# design.net
KiCad netlist of a schematic drawn in EasyEDA Pro
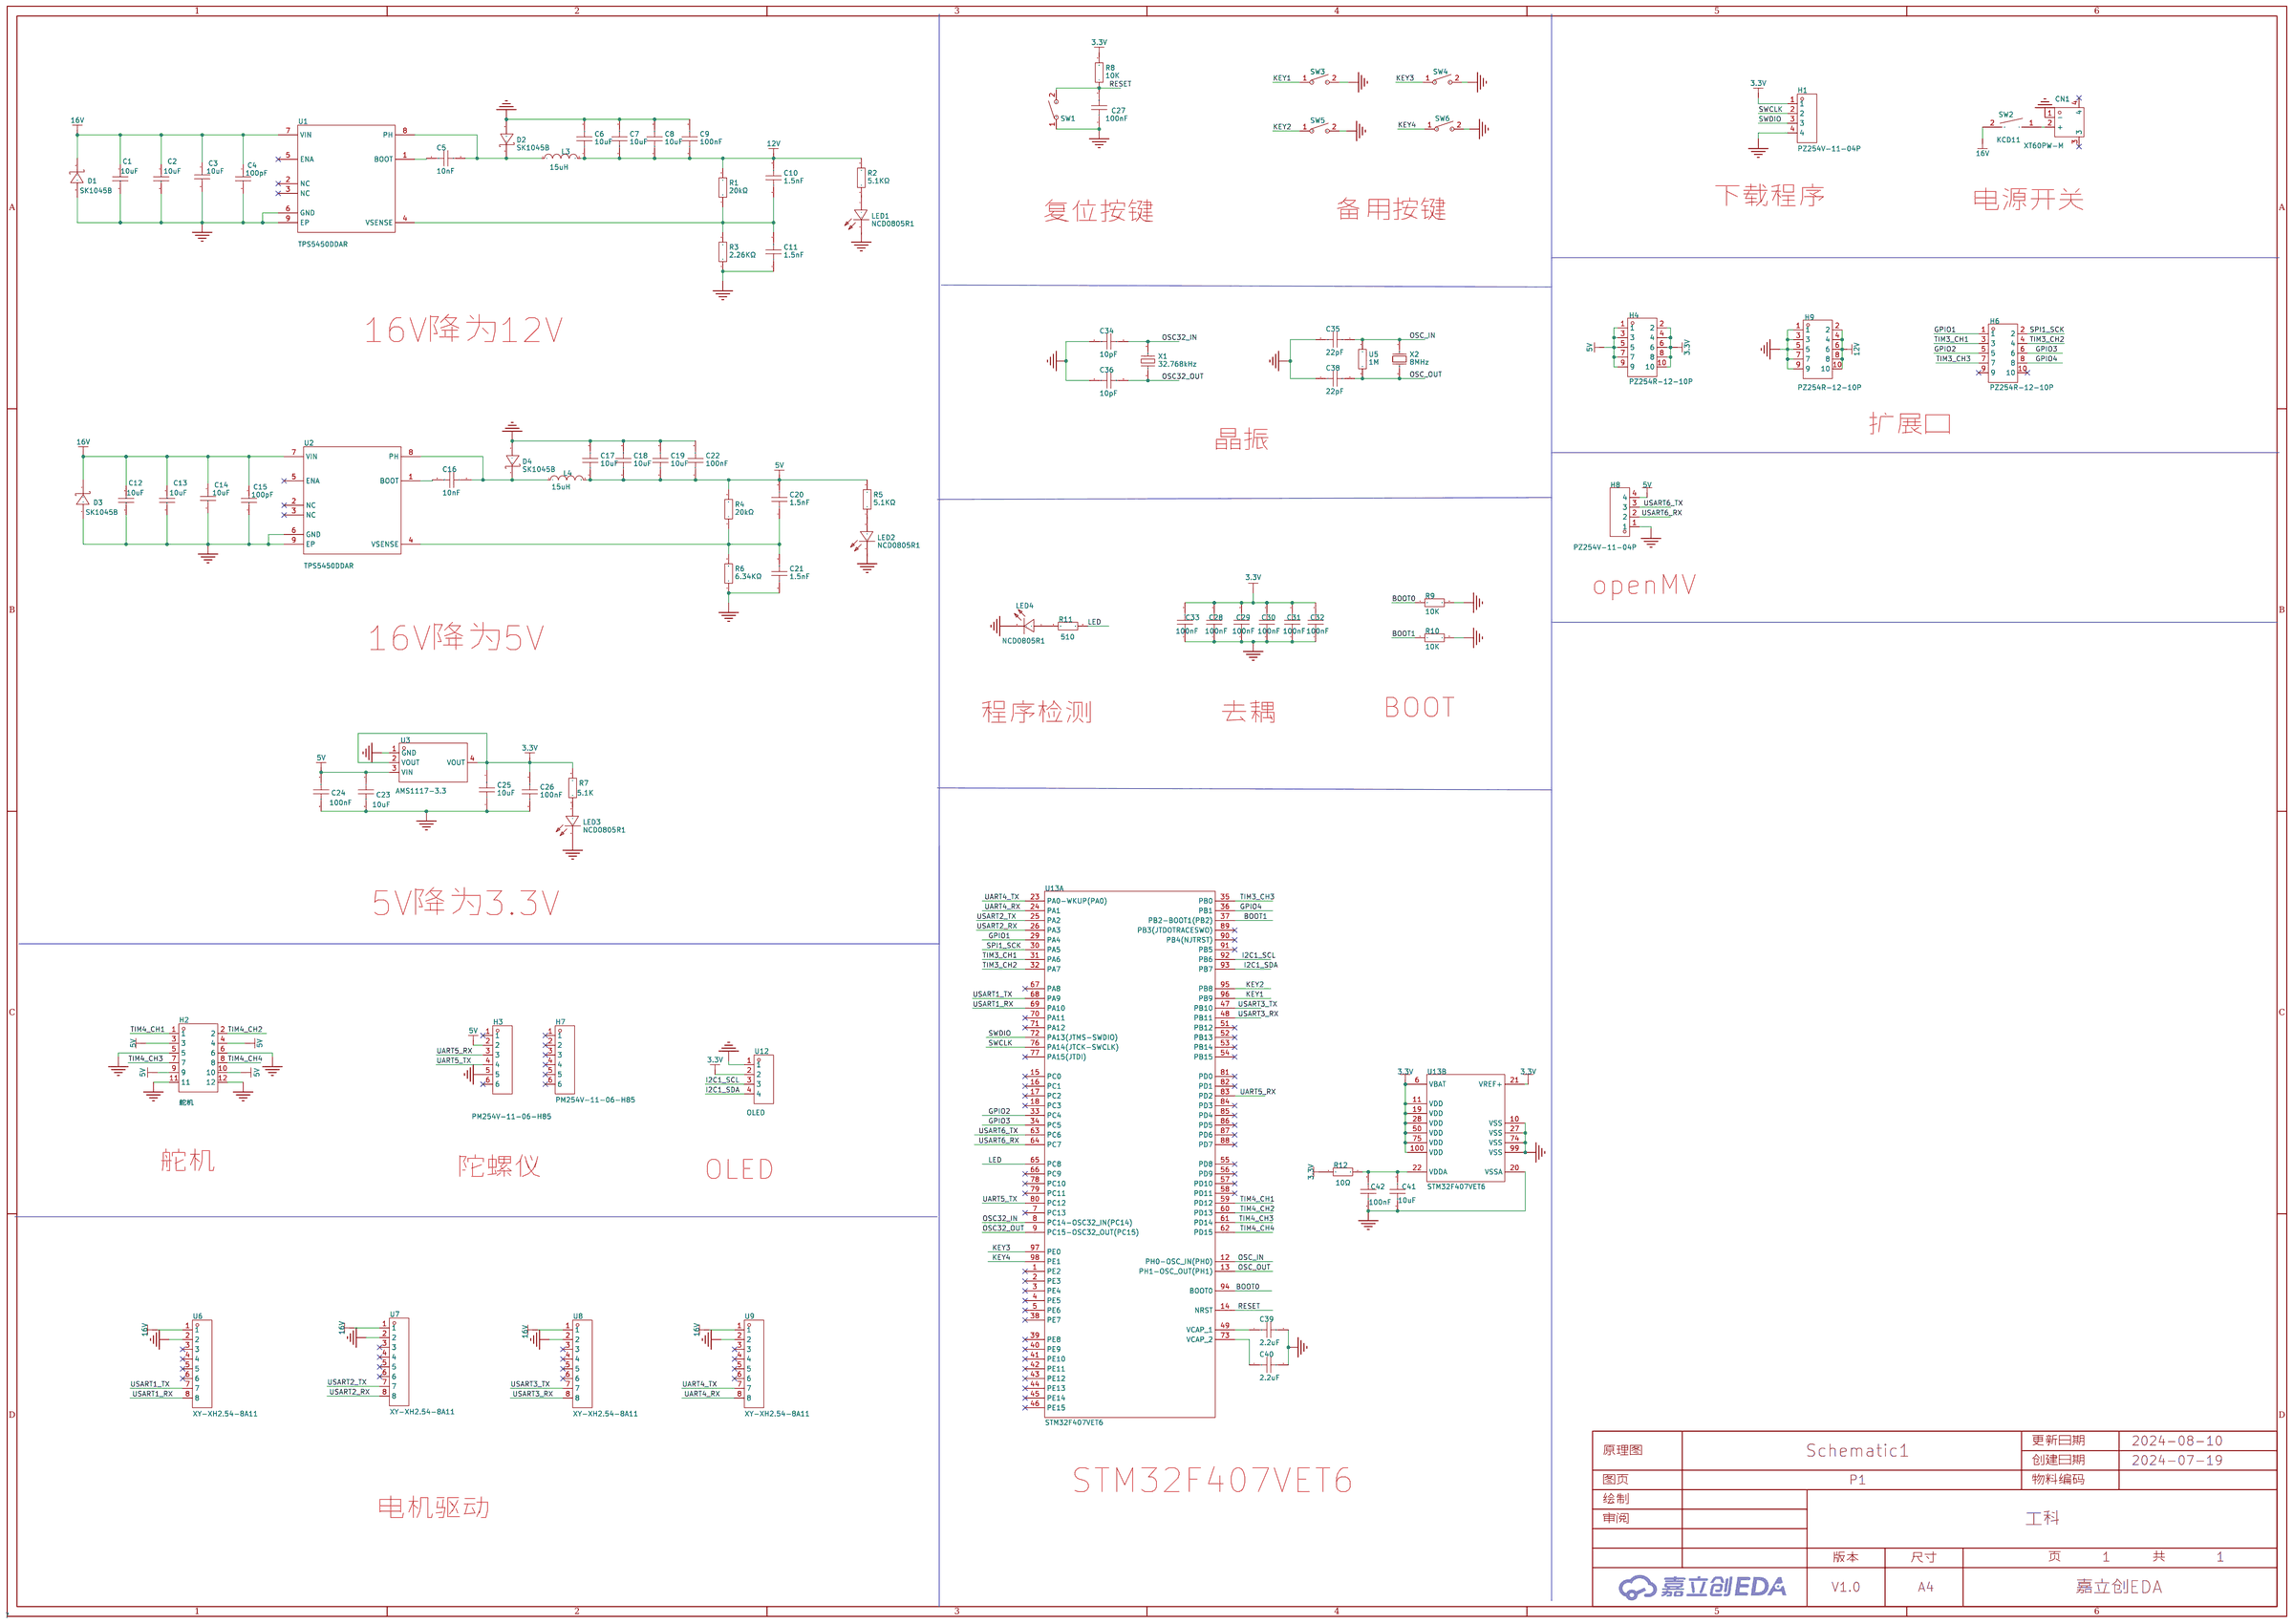
[diagram p0: schematic sheet]

(export (version "E")
  (design (tool "Eeschema 10.0.6"))
  (components
    (comp (ref "C1")
      (value "10uF")
      (footprint "easyedapro:C0805")
      (description "容值:100nF;精度:±10%;额定电压:50V;材质(温度系数):X7R;")
      (fields
        (field (name "Manufacturer Part") "CC0805KRX7R9BB104")
        (field (name "Manufacturer") "YAGEO(国巨)")
      )
      (libsource (lib "easyedapro") (part "CC0805KRX7R9BB104"))
    )
    (comp (ref "C2")
      (value "10uF")
      (footprint "easyedapro:C0805")
      (description "容值:100nF;精度:±10%;额定电压:50V;材质(温度系数):X7R;")
      (fields
        (field (name "Manufacturer Part") "CC0805KRX7R9BB104")
        (field (name "Manufacturer") "YAGEO(国巨)")
      )
      (libsource (lib "easyedapro") (part "CC0805KRX7R9BB104"))
    )
    (comp (ref "C3")
      (value "10uF")
      (footprint "easyedapro:C0805")
      (description "容值:100nF;精度:±10%;额定电压:50V;材质(温度系数):X7R;")
      (fields
        (field (name "Manufacturer Part") "CC0805KRX7R9BB104")
        (field (name "Manufacturer") "YAGEO(国巨)")
      )
      (libsource (lib "easyedapro") (part "CC0805KRX7R9BB104"))
    )
    (comp (ref "C4")
      (value "100pF")
      (footprint "easyedapro:C0805")
      (description "容值:100nF;精度:±10%;额定电压:50V;材质(温度系数):X7R;")
      (fields
        (field (name "Manufacturer Part") "CC0805KRX7R9BB104")
        (field (name "Manufacturer") "YAGEO(国巨)")
      )
      (libsource (lib "easyedapro") (part "CC0805KRX7R9BB104"))
    )
    (comp (ref "C5")
      (value "10nF")
      (footprint "easyedapro:C0805")
      (libsource (lib "easyedapro") (part "CapAcitance"))
    )
    (comp (ref "C6")
      (value "10uF")
      (footprint "easyedapro:C0805")
      (libsource (lib "easyedapro") (part "CapAcitance"))
    )
    (comp (ref "C7")
      (value "10uF")
      (footprint "easyedapro:C0805")
      (libsource (lib "easyedapro") (part "CapAcitance"))
    )
    (comp (ref "C8")
      (value "10uF")
      (footprint "easyedapro:C0805")
      (libsource (lib "easyedapro") (part "CapAcitance"))
    )
    (comp (ref "C9")
      (value "100nF")
      (footprint "easyedapro:C0805")
      (libsource (lib "easyedapro") (part "CapAcitance"))
    )
    (comp (ref "C10")
      (value "1.5nF")
      (footprint "easyedapro:C0805")
      (libsource (lib "easyedapro") (part "CapAcitance"))
    )
    (comp (ref "C11")
      (value "1.5nF")
      (footprint "easyedapro:C0805")
      (libsource (lib "easyedapro") (part "CapAcitance"))
    )
    (comp (ref "C12")
      (value "10uF")
      (footprint "easyedapro:C0805")
      (description "容值:100nF;精度:±10%;额定电压:50V;材质(温度系数):X7R;")
      (fields
        (field (name "Manufacturer Part") "CC0805KRX7R9BB104")
        (field (name "Manufacturer") "YAGEO(国巨)")
      )
      (libsource (lib "easyedapro") (part "CC0805KRX7R9BB104"))
    )
    (comp (ref "C13")
      (value "10uF")
      (footprint "easyedapro:C0805")
      (description "容值:100nF;精度:±10%;额定电压:50V;材质(温度系数):X7R;")
      (fields
        (field (name "Manufacturer Part") "CC0805KRX7R9BB104")
        (field (name "Manufacturer") "YAGEO(国巨)")
      )
      (libsource (lib "easyedapro") (part "CC0805KRX7R9BB104"))
    )
    (comp (ref "C14")
      (value "10uF")
      (footprint "easyedapro:C0805")
      (description "容值:100nF;精度:±10%;额定电压:50V;材质(温度系数):X7R;")
      (fields
        (field (name "Manufacturer Part") "CC0805KRX7R9BB104")
        (field (name "Manufacturer") "YAGEO(国巨)")
      )
      (libsource (lib "easyedapro") (part "CC0805KRX7R9BB104"))
    )
    (comp (ref "C15")
      (value "100pF")
      (footprint "easyedapro:C0805")
      (description "容值:100nF;精度:±10%;额定电压:50V;材质(温度系数):X7R;")
      (fields
        (field (name "Manufacturer Part") "CC0805KRX7R9BB104")
        (field (name "Manufacturer") "YAGEO(国巨)")
      )
      (libsource (lib "easyedapro") (part "CC0805KRX7R9BB104"))
    )
    (comp (ref "C16")
      (value "10nF")
      (footprint "easyedapro:C0805")
      (libsource (lib "easyedapro") (part "CapAcitance"))
    )
    (comp (ref "C17")
      (value "10uF")
      (footprint "easyedapro:C0805")
      (libsource (lib "easyedapro") (part "CapAcitance"))
    )
    (comp (ref "C18")
      (value "10uF")
      (footprint "easyedapro:C0805")
      (libsource (lib "easyedapro") (part "CapAcitance"))
    )
    (comp (ref "C19")
      (value "10uF")
      (footprint "easyedapro:C0805")
      (libsource (lib "easyedapro") (part "CapAcitance"))
    )
    (comp (ref "C20")
      (value "1.5nF")
      (footprint "easyedapro:C0805")
      (libsource (lib "easyedapro") (part "CapAcitance"))
    )
    (comp (ref "C21")
      (value "1.5nF")
      (footprint "easyedapro:C0805")
      (libsource (lib "easyedapro") (part "CapAcitance"))
    )
    (comp (ref "C22")
      (value "100nF")
      (footprint "easyedapro:C0805")
      (libsource (lib "easyedapro") (part "CapAcitance"))
    )
    (comp (ref "C23")
      (value "10uF")
      (footprint "easyedapro:C0805")
      (libsource (lib "easyedapro") (part "CapAcitance"))
    )
    (comp (ref "C24")
      (value "100nF")
      (footprint "easyedapro:C0805")
      (libsource (lib "easyedapro") (part "CapAcitance"))
    )
    (comp (ref "C25")
      (value "10uF")
      (footprint "easyedapro:C0805")
      (libsource (lib "easyedapro") (part "CapAcitance"))
    )
    (comp (ref "C26")
      (value "100nF")
      (footprint "easyedapro:C0805")
      (libsource (lib "easyedapro") (part "CapAcitance"))
    )
    (comp (ref "C27")
      (value "100nF")
      (footprint "easyedapro:C0805")
      (libsource (lib "easyedapro") (part "CapAcitance"))
    )
    (comp (ref "C28")
      (value "100nF")
      (footprint "easyedapro:C0805")
      (libsource (lib "easyedapro") (part "CapAcitance"))
    )
    (comp (ref "C29")
      (value "100nF")
      (footprint "easyedapro:C0805")
      (libsource (lib "easyedapro") (part "CapAcitance"))
    )
    (comp (ref "C30")
      (value "100nF")
      (footprint "easyedapro:C0805")
      (libsource (lib "easyedapro") (part "CapAcitance"))
    )
    (comp (ref "C31")
      (value "100nF")
      (footprint "easyedapro:C0805")
      (libsource (lib "easyedapro") (part "CapAcitance"))
    )
    (comp (ref "C32")
      (value "100nF")
      (footprint "easyedapro:C0805")
      (libsource (lib "easyedapro") (part "CapAcitance"))
    )
    (comp (ref "C33")
      (value "100nF")
      (footprint "easyedapro:C0805")
      (libsource (lib "easyedapro") (part "CapAcitance"))
    )
    (comp (ref "C34")
      (value "10pF")
      (footprint "easyedapro:C0805")
      (libsource (lib "easyedapro") (part "CapAcitance"))
    )
    (comp (ref "C35")
      (value "22pF")
      (footprint "easyedapro:C0805")
      (libsource (lib "easyedapro") (part "CapAcitance"))
    )
    (comp (ref "C36")
      (value "10pF")
      (footprint "easyedapro:C0805")
      (libsource (lib "easyedapro") (part "CapAcitance"))
    )
    (comp (ref "C38")
      (value "22pF")
      (footprint "easyedapro:C0805")
      (libsource (lib "easyedapro") (part "CapAcitance"))
    )
    (comp (ref "C39")
      (value "2.2uF")
      (footprint "easyedapro:C0805")
      (libsource (lib "easyedapro") (part "CapAcitance"))
    )
    (comp (ref "C40")
      (value "2.2uF")
      (footprint "easyedapro:C0805")
      (libsource (lib "easyedapro") (part "CapAcitance"))
    )
    (comp (ref "C41")
      (value "10uF")
      (footprint "easyedapro:C0805")
      (libsource (lib "easyedapro") (part "CapAcitance"))
    )
    (comp (ref "C42")
      (value "100nF")
      (footprint "easyedapro:C0805")
      (libsource (lib "easyedapro") (part "CapAcitance"))
    )
    (comp (ref "CN1")
      (value "XT60PW-M")
      (footprint "easyedapro:CONN-TH_XT60PW-M")
      (description "类别:-;类型1:-;")
      (fields (field (name "Manufacturer") "AMASS(艾迈斯)"))
      (libsource (lib "easyedapro") (part "XT60PW-M"))
    )
    (comp (ref "D1")
      (value "SK1045B")
      (footprint "easyedapro:SMB_L4.6-W3.6-LS5.3-RD")
      (description "二极管配置:独立式;正向压降(Vf):550mV@10A;直流反向耐压(Vr):45V;整流电流:10A;")
      (fields (field (name "Manufacturer") "MDD(辰达半导体)"))
      (libsource (lib "easyedapro") (part "SK1045_C65017"))
    )
    (comp (ref "D2")
      (value "SK1045B")
      (footprint "easyedapro:SMB_L4.6-W3.6-LS5.3-RD")
      (description "二极管配置:独立式;正向压降(Vf):550mV@10A;直流反向耐压(Vr):45V;整流电流:10A;")
      (fields (field (name "Manufacturer") "MDD(辰达半导体)"))
      (libsource (lib "easyedapro") (part "SK1045_C65017"))
    )
    (comp (ref "D3")
      (value "SK1045B")
      (footprint "easyedapro:SMB_L4.6-W3.6-LS5.3-RD")
      (description "二极管配置:独立式;正向压降(Vf):550mV@10A;直流反向耐压(Vr):45V;整流电流:10A;")
      (fields (field (name "Manufacturer") "MDD(辰达半导体)"))
      (libsource (lib "easyedapro") (part "SK1045_C65017"))
    )
    (comp (ref "D4")
      (value "SK1045B")
      (footprint "easyedapro:SMB_L4.6-W3.6-LS5.3-RD")
      (description "二极管配置:独立式;正向压降(Vf):550mV@10A;直流反向耐压(Vr):45V;整流电流:10A;")
      (fields (field (name "Manufacturer") "MDD(辰达半导体)"))
      (libsource (lib "easyedapro") (part "SK1045_C65017"))
    )
    (comp (ref "H1")
      (value "PZ254V-11-04P")
      (footprint "easyedapro:HDR-TH_4P-P2.54-V-M")
      (fields (field (name "Manufacturer") "XFCN(兴飞)"))
      (libsource (lib "easyedapro") (part "PZ254V-11-04P_C2691448"))
    )
    (comp (ref "H2")
      (value "舵机")
      (footprint "easyedapro:HDR-TH_12P-P2.54-H-M-R2-C6-S2.54")
      (fields (field (name "Manufacturer") "XFCN(兴飞)"))
      (libsource (lib "easyedapro") (part "PZ254R-12-12P"))
    )
    (comp (ref "H3")
      (value "PM254V-11-06-H85")
      (footprint "easyedapro:HDR-TH_6P-P2.54-V-F")
      (fields (field (name "Manufacturer") "XFCN(兴飞)"))
      (libsource (lib "easyedapro") (part "PM254V-11-06-H85"))
    )
    (comp (ref "H4")
      (value "PZ254R-12-10P")
      (footprint "easyedapro:HDR-TH_10P-P2.54-H-M-R2-C5-S2.54")
      (fields (field (name "Manufacturer") "XFCN(兴飞)"))
      (libsource (lib "easyedapro") (part "PZ254R-12-10P"))
    )
    (comp (ref "H6")
      (value "PZ254R-12-10P")
      (footprint "easyedapro:HDR-TH_10P-P2.54-H-M-R2-C5-S2.54")
      (fields (field (name "Manufacturer") "XFCN(兴飞)"))
      (libsource (lib "easyedapro") (part "PZ254R-12-10P"))
    )
    (comp (ref "H7")
      (value "PM254V-11-06-H85")
      (footprint "easyedapro:HDR-TH_6P-P2.54-V-F")
      (fields (field (name "Manufacturer") "XFCN(兴飞)"))
      (libsource (lib "easyedapro") (part "PM254V-11-06-H85"))
    )
    (comp (ref "H8")
      (value "PZ254V-11-04P")
      (footprint "easyedapro:HDR-TH_4P-P2.54-V-M")
      (fields (field (name "Manufacturer") "XFCN(兴飞)"))
      (libsource (lib "easyedapro") (part "PZ254V-11-04P_C2691448"))
    )
    (comp (ref "H9")
      (value "PZ254R-12-10P")
      (footprint "easyedapro:HDR-TH_10P-P2.54-H-M-R2-C5-S2.54")
      (fields (field (name "Manufacturer") "XFCN(兴飞)"))
      (libsource (lib "easyedapro") (part "PZ254R-12-10P"))
    )
    (comp (ref "L3")
      (value "15uH")
      (footprint "easyedapro:IND-SMD_L11.5-W10.0_APS10A40")
      (description "电感值:15uH;精度:±20%;额定电流:6.55A;饱和电流(Isat):7A;")
      (fields (field (name "Manufacturer Part") "APS10A40M150") (field (name "Manufacturer") "Coilank(驰兴电感)"))
      (libsource (lib "easyedapro") (part "APS10A40M150"))
    )
    (comp (ref "L4")
      (value "15uH")
      (footprint "easyedapro:IND-SMD_L11.5-W10.0_APS10A40")
      (description "电感值:15uH;精度:±20%;额定电流:6.55A;饱和电流(Isat):7A;")
      (fields (field (name "Manufacturer Part") "APS10A40M150") (field (name "Manufacturer") "Coilank(驰兴电感)"))
      (libsource (lib "easyedapro") (part "APS10A40M150"))
    )
    (comp (ref "LED1")
      (value "NCD0805R1")
      (footprint "easyedapro:LED0805-R-RD")
      (fields (field (name "Manufacturer") "国星光电"))
      (libsource (lib "easyedapro") (part "FC-2012HRK-620D"))
    )
    (comp (ref "LED2")
      (value "NCD0805R1")
      (footprint "easyedapro:LED0805-R-RD")
      (fields (field (name "Manufacturer") "国星光电"))
      (libsource (lib "easyedapro") (part "FC-2012HRK-620D"))
    )
    (comp (ref "LED3")
      (value "NCD0805R1")
      (footprint "easyedapro:LED0805-R-RD")
      (fields (field (name "Manufacturer") "国星光电"))
      (libsource (lib "easyedapro") (part "FC-2012HRK-620D"))
    )
    (comp (ref "LED4")
      (value "NCD0805R1")
      (footprint "easyedapro:LED0805-R-RD")
      (fields (field (name "Manufacturer") "国星光电"))
      (libsource (lib "easyedapro") (part "FC-2012HRK-620D"))
    )
    (comp (ref "R1") (value "20kΩ") (footprint "easyedapro:R0805") (libsource (lib "easyedapro") (part "电阻")))
    (comp (ref "R2")
      (value "5.1KΩ")
      (footprint "easyedapro:R0805")
      (libsource (lib "easyedapro") (part "电阻"))
    )
    (comp (ref "R3")
      (value "2.26KΩ")
      (footprint "easyedapro:R0805")
      (libsource (lib "easyedapro") (part "电阻"))
    )
    (comp (ref "R4") (value "20kΩ") (footprint "easyedapro:R0805") (libsource (lib "easyedapro") (part "电阻")))
    (comp (ref "R5")
      (value "5.1KΩ")
      (footprint "easyedapro:R0805")
      (libsource (lib "easyedapro") (part "电阻"))
    )
    (comp (ref "R6")
      (value "6.34KΩ")
      (footprint "easyedapro:R0805")
      (libsource (lib "easyedapro") (part "电阻"))
    )
    (comp (ref "R7") (value "5.1K") (footprint "easyedapro:R0805") (libsource (lib "easyedapro") (part "电阻")))
    (comp (ref "R8") (value "10K") (footprint "easyedapro:R0805") (libsource (lib "easyedapro") (part "电阻")))
    (comp (ref "R9") (value "10K") (footprint "easyedapro:R0805") (libsource (lib "easyedapro") (part "电阻")))
    (comp (ref "R10") (value "10K") (footprint "easyedapro:R0805") (libsource (lib "easyedapro") (part "电阻")))
    (comp (ref "R11") (value "510") (footprint "easyedapro:R0805") (libsource (lib "easyedapro") (part "电阻")))
    (comp (ref "R12") (value "10Ω") (footprint "easyedapro:R0805") (libsource (lib "easyedapro") (part "电阻")))
    (comp (ref "SW1")
      (value "轻触按键3*6*2.5")
      (footprint "easyedapro:SW-SMD_L6.0-W3.6-LS8.0")
      (libsource (lib "easyedapro") (part "轻触按键3*6*2.5"))
    )
    (comp (ref "SW2")
      (value "KCD11")
      (footprint "easyedapro:SW-TH_RS601HL-1010011BB")
      (description "带灯:无;引脚样式:焊片;额定电流:3A;额定电压(AC):250V;额定电压(DC):-;电路结构:单刀单掷;机械寿命:1万次;")
      (fields (field (name "Manufacturer") "HCTL(华灿天禄)"))
      (libsource (lib "easyedapro") (part "RS601HL-1010011BB"))
    )
    (comp (ref "SW3")
      (value "轻触按键3*6*2.5")
      (footprint "easyedapro:SW-SMD_L6.0-W3.6-LS8.0")
      (libsource (lib "easyedapro") (part "轻触按键3*6*2.5"))
    )
    (comp (ref "SW4")
      (value "轻触按键3*6*2.5")
      (footprint "easyedapro:SW-SMD_L6.0-W3.6-LS8.0")
      (libsource (lib "easyedapro") (part "轻触按键3*6*2.5"))
    )
    (comp (ref "SW5")
      (value "轻触按键3*6*2.5")
      (footprint "easyedapro:SW-SMD_L6.0-W3.6-LS8.0")
      (libsource (lib "easyedapro") (part "轻触按键3*6*2.5"))
    )
    (comp (ref "SW6")
      (value "轻触按键3*6*2.5")
      (footprint "easyedapro:SW-SMD_L6.0-W3.6-LS8.0")
      (libsource (lib "easyedapro") (part "轻触按键3*6*2.5"))
    )
    (comp (ref "U1")
      (value "TPS5450DDAR")
      (footprint "easyedapro:SOP-8_L4.9-W3.9-P1.27-LS6.0-BL-EP")
      (description "功能类型:降压型;输出类型:可调;输入电压:5.5V~36V;输出电压:1.221V~31.32V;输出电流(最大值):5A;")
      (fields (field (name "Manufacturer") "TI(德州仪器)"))
      (libsource (lib "easyedapro") (part "TPS5450DDAR"))
    )
    (comp (ref "U2")
      (value "TPS5450DDAR")
      (footprint "easyedapro:SOP-8_L4.9-W3.9-P1.27-LS6.0-BL-EP")
      (description "功能类型:降压型;输出类型:可调;输入电压:5.5V~36V;输出电压:1.221V~31.32V;输出电流(最大值):5A;")
      (fields (field (name "Manufacturer") "TI(德州仪器)"))
      (libsource (lib "easyedapro") (part "TPS5450DDAR"))
    )
    (comp (ref "U3")
      (value "AMS1117-3.3")
      (footprint "easyedapro:SOT-223-3_L6.5-W3.4-P2.30-LS7.0-BR")
      (description "输出类型:固定;最大输入电压:-;输出电压:3.3V;最大输出电流:1A;电源纹波抑制比(PSRR):72dB@(120Hz);输出极性:正极;")
      (fields (field (name "Manufacturer") "AMS"))
      (libsource (lib "easyedapro") (part "AMS1117-3.3"))
    )
    (comp (ref "U5") (value "1M") (footprint "easyedapro:R0805") (libsource (lib "easyedapro") (part "电阻")))
    (comp (ref "U6")
      (value "XY-XH2.54-8A11")
      (footprint "easyedapro:HDR-TH_8P-P2.50-V-F-2")
      (description "插针结构:1x8P;间距:2.54mm;安装方式:直插;总PIN数:8P;排数:1;每排PIN数:8;行距:2.54mm;额定电流:2A;工作温度范围:-25°C~+85°C;")
      (fields (field (name "Manufacturer") "XYECONN(辛译)"))
      (libsource (lib "easyedapro") (part "XY-XH2.54-8A11"))
    )
    (comp (ref "U7")
      (value "XY-XH2.54-8A11")
      (footprint "easyedapro:HDR-TH_8P-P2.50-V-F-2")
      (description "插针结构:1x8P;间距:2.54mm;安装方式:直插;总PIN数:8P;排数:1;每排PIN数:8;行距:2.54mm;额定电流:2A;工作温度范围:-25°C~+85°C;")
      (fields (field (name "Manufacturer") "XYECONN(辛译)"))
      (libsource (lib "easyedapro") (part "XY-XH2.54-8A11"))
    )
    (comp (ref "U8")
      (value "XY-XH2.54-8A11")
      (footprint "easyedapro:HDR-TH_8P-P2.50-V-F-2")
      (description "插针结构:1x8P;间距:2.54mm;安装方式:直插;总PIN数:8P;排数:1;每排PIN数:8;行距:2.54mm;额定电流:2A;工作温度范围:-25°C~+85°C;")
      (fields (field (name "Manufacturer") "XYECONN(辛译)"))
      (libsource (lib "easyedapro") (part "XY-XH2.54-8A11"))
    )
    (comp (ref "U9")
      (value "XY-XH2.54-8A11")
      (footprint "easyedapro:HDR-TH_8P-P2.50-V-F-2")
      (description "插针结构:1x8P;间距:2.54mm;安装方式:直插;总PIN数:8P;排数:1;每排PIN数:8;行距:2.54mm;额定电流:2A;工作温度范围:-25°C~+85°C;")
      (fields (field (name "Manufacturer") "XYECONN(辛译)"))
      (libsource (lib "easyedapro") (part "XY-XH2.54-8A11"))
    )
    (comp (ref "U12")
      (value "OLED")
      (footprint "easyedapro:HDR-TH_4P-P2.54-H-F-W10.0-N")
      (fields (field (name "Manufacturer") "HCTL(华灿天禄)"))
      (libsource (lib "easyedapro") (part "PM254-1-04-W-8.5"))
    )
    (comp (ref "U13")
      (value "STM32F407VET6")
      (footprint "easyedapro:LQFP-100_L14.0-W14.0-P0.50-LS16.0-BL")
      (description "CPU内核:CM4;程序存储容量:512KB;RAM总容量:192KB;GPIO端口数量:82;工作电压范围:1.8V~3.6V;CPU最大主频:168MHz;程序存储器类型:FLASH;")
      (fields (field (name "Manufacturer") "ST(意法半导体)"))
      (libsource (lib "easyedapro") (part "STM32F407VET6"))
    )
    (comp (ref "X1")
      (value "32.768kHz")
      (footprint "easyedapro:OSC-SMD_L3.2-W1.5")
      (description "晶振类型:贴片晶振;频率:32.768kHz;常温频差:±20ppm;外接负载电容:12.5pF;频率稳定度(全温):-;")
      (fields (field (name "Manufacturer Part") "X321532768KGD2SI") (field (name "Manufacturer") "YXC(扬兴晶振)"))
      (libsource (lib "easyedapro") (part "X321532768KGD2SI"))
    )
    (comp (ref "X2")
      (value "8MHz")
      (footprint "easyedapro:HC-49US_L11.5-W4.5-P4.88")
      (description "晶振类型:直插晶振;频率:8MHz;常温频差:±30ppm;外接负载电容:20pF;频率稳定度(全温):±30ppm;")
      (fields (field (name "Manufacturer Part") "TAXD8M2GLFBET2T") (field (name "Manufacturer") "YJX(雅晶鑫)"))
      (libsource (lib "easyedapro") (part "HC-49S 8MHz 20pF 30PPM"))
    )
  )
  (nets
    (net (code "1") (name "/BOOT0") (class "Default")
      (node (ref "R9") (pin "1") (pinfunction "1_1") (pintype "input"))
      (node (ref "U13") (pin "94") (pinfunction "BOOT0_94") (pintype "unspecified"))
    )
    (net (code "2") (name "/BOOT1") (class "Default")
      (node (ref "R10") (pin "1") (pinfunction "1_1") (pintype "input"))
      (node (ref "U13") (pin "37") (pinfunction "PB2-BOOT1(PB2)_37") (pintype "bidirectional"))
    )
    (net (code "3") (name "/GPIO1") (class "Default")
      (node (ref "H6") (pin "1") (pinfunction "1_1") (pintype "unspecified"))
      (node (ref "U13") (pin "29") (pinfunction "PA4_29") (pintype "bidirectional"))
    )
    (net (code "4") (name "/GPIO2") (class "Default")
      (node (ref "H6") (pin "5") (pinfunction "5_5") (pintype "unspecified"))
      (node (ref "U13") (pin "33") (pinfunction "PC4_33") (pintype "bidirectional"))
    )
    (net (code "5") (name "/GPIO3") (class "Default")
      (node (ref "H6") (pin "6") (pinfunction "6_6") (pintype "unspecified"))
      (node (ref "U13") (pin "34") (pinfunction "PC5_34") (pintype "bidirectional"))
    )
    (net (code "6") (name "/GPIO4") (class "Default")
      (node (ref "H6") (pin "8") (pinfunction "8_8") (pintype "unspecified"))
      (node (ref "U13") (pin "36") (pinfunction "PB1_36") (pintype "bidirectional"))
    )
    (net (code "7") (name "/I2C1_SCL") (class "Default")
      (node (ref "U12") (pin "3") (pinfunction "3_3") (pintype "unspecified"))
      (node (ref "U13") (pin "92") (pinfunction "PB6_92") (pintype "bidirectional"))
    )
    (net (code "8") (name "/I2C1_SDA") (class "Default")
      (node (ref "U12") (pin "4") (pinfunction "4_4") (pintype "unspecified"))
      (node (ref "U13") (pin "93") (pinfunction "PB7_93") (pintype "bidirectional"))
    )
    (net (code "9") (name "/KEY1") (class "Default")
      (node (ref "SW3") (pin "1") (pinfunction "1_1") (pintype "unspecified"))
      (node (ref "U13") (pin "96") (pinfunction "PB9_96") (pintype "bidirectional"))
    )
    (net (code "10") (name "/KEY2") (class "Default")
      (node (ref "SW5") (pin "1") (pinfunction "1_1") (pintype "unspecified"))
      (node (ref "U13") (pin "95") (pinfunction "PB8_95") (pintype "bidirectional"))
    )
    (net (code "11") (name "/KEY3") (class "Default")
      (node (ref "SW4") (pin "1") (pinfunction "1_1") (pintype "unspecified"))
      (node (ref "U13") (pin "97") (pinfunction "PE0_97") (pintype "bidirectional"))
    )
    (net (code "12") (name "/KEY4") (class "Default")
      (node (ref "SW6") (pin "1") (pinfunction "1_1") (pintype "unspecified"))
      (node (ref "U13") (pin "98") (pinfunction "PE1_98") (pintype "bidirectional"))
    )
    (net (code "13") (name "/LED") (class "Default")
      (node (ref "R11") (pin "2") (pinfunction "2_2") (pintype "input"))
      (node (ref "U13") (pin "65") (pinfunction "PC8_65") (pintype "bidirectional"))
    )
    (net (code "14") (name "/OSC32_IN") (class "Default")
      (node (ref "C34") (pin "1") (pinfunction "1_1") (pintype "input"))
      (node (ref "U13") (pin "8") (pinfunction "PC14-OSC32_IN(PC14)_8") (pintype "bidirectional"))
      (node (ref "X1") (pin "2") (pinfunction "2_2") (pintype "input"))
    )
    (net (code "15") (name "/OSC32_OUT") (class "Default")
      (node (ref "C36") (pin "2") (pinfunction "2_2") (pintype "input"))
      (node (ref "U13") (pin "9") (pinfunction "PC15-OSC32_OUT(PC15)_9") (pintype "bidirectional"))
      (node (ref "X1") (pin "1") (pinfunction "1_1") (pintype "input"))
    )
    (net (code "16") (name "/OSC_IN") (class "Default")
      (node (ref "C35") (pin "1") (pinfunction "1_1") (pintype "input"))
      (node (ref "U13") (pin "12") (pinfunction "PH0-OSC_IN(PH0)_12") (pintype "bidirectional"))
      (node (ref "U5") (pin "2") (pinfunction "2_2") (pintype "input"))
      (node (ref "X2") (pin "2") (pinfunction "OSC2_2") (pintype "input"))
    )
    (net (code "17") (name "/OSC_OUT") (class "Default")
      (node (ref "C38") (pin "2") (pinfunction "2_2") (pintype "input"))
      (node (ref "U13") (pin "13") (pinfunction "PH1-OSC_OUT(PH1)_13") (pintype "bidirectional"))
      (node (ref "U5") (pin "1") (pinfunction "1_1") (pintype "input"))
      (node (ref "X2") (pin "1") (pinfunction "OSC1_1") (pintype "input"))
    )
    (net (code "18") (name "/RESET") (class "Default")
      (node (ref "C27") (pin "2") (pinfunction "2_2") (pintype "input"))
      (node (ref "R8") (pin "1") (pinfunction "1_1") (pintype "input"))
      (node (ref "SW1") (pin "2") (pinfunction "2_2") (pintype "unspecified"))
      (node (ref "U13") (pin "14") (pinfunction "NRST_14") (pintype "bidirectional"))
    )
    (net (code "19") (name "/SPI1_SCK") (class "Default")
      (node (ref "H6") (pin "2") (pinfunction "2_2") (pintype "unspecified"))
      (node (ref "U13") (pin "30") (pinfunction "PA5_30") (pintype "bidirectional"))
    )
    (net (code "20") (name "/SWCLK") (class "Default")
      (node (ref "H1") (pin "2") (pinfunction "2_2") (pintype "unspecified"))
      (node (ref "U13") (pin "76") (pinfunction "PA14(JTCK-SWCLK)_76") (pintype "bidirectional"))
    )
    (net (code "21") (name "/SWDIO") (class "Default")
      (node (ref "H1") (pin "3") (pinfunction "3_3") (pintype "unspecified"))
      (node (ref "U13") (pin "72") (pinfunction "PA13(JTMS-SWDIO)_72") (pintype "bidirectional"))
    )
    (net (code "22") (name "/TIM3_CH1") (class "Default")
      (node (ref "H6") (pin "3") (pinfunction "3_3") (pintype "unspecified"))
      (node (ref "U13") (pin "31") (pinfunction "PA6_31") (pintype "bidirectional"))
    )
    (net (code "23") (name "/TIM3_CH2") (class "Default")
      (node (ref "H6") (pin "4") (pinfunction "4_4") (pintype "unspecified"))
      (node (ref "U13") (pin "32") (pinfunction "PA7_32") (pintype "bidirectional"))
    )
    (net (code "24") (name "/TIM3_CH3") (class "Default")
      (node (ref "H6") (pin "7") (pinfunction "7_7") (pintype "unspecified"))
      (node (ref "U13") (pin "35") (pinfunction "PB0_35") (pintype "bidirectional"))
    )
    (net (code "25") (name "/TIM4_CH1") (class "Default")
      (node (ref "H2") (pin "1") (pinfunction "1_1") (pintype "unspecified"))
      (node (ref "U13") (pin "59") (pinfunction "PD12_59") (pintype "bidirectional"))
    )
    (net (code "26") (name "/TIM4_CH2") (class "Default")
      (node (ref "H2") (pin "2") (pinfunction "2_2") (pintype "unspecified"))
      (node (ref "U13") (pin "60") (pinfunction "PD13_60") (pintype "bidirectional"))
    )
    (net (code "27") (name "/TIM4_CH3") (class "Default")
      (node (ref "H2") (pin "7") (pinfunction "7_7") (pintype "unspecified"))
      (node (ref "U13") (pin "61") (pinfunction "PD14_61") (pintype "bidirectional"))
    )
    (net (code "28") (name "/TIM4_CH4") (class "Default")
      (node (ref "H2") (pin "8") (pinfunction "8_8") (pintype "unspecified"))
      (node (ref "U13") (pin "62") (pinfunction "PD15_62") (pintype "bidirectional"))
    )
    (net (code "29") (name "/UART4_RX") (class "Default")
      (node (ref "U13") (pin "24") (pinfunction "PA1_24") (pintype "bidirectional"))
      (node (ref "U9") (pin "8") (pinfunction "8_8") (pintype "unspecified"))
    )
    (net (code "30") (name "/UART4_TX") (class "Default")
      (node (ref "U13") (pin "23") (pinfunction "PA0-WKUP(PA0)_23") (pintype "bidirectional"))
      (node (ref "U9") (pin "7") (pinfunction "7_7") (pintype "unspecified"))
    )
    (net (code "31") (name "/UART5_RX") (class "Default")
      (node (ref "H3") (pin "3") (pinfunction "3_3") (pintype "unspecified"))
      (node (ref "U13") (pin "83") (pinfunction "PD2_83") (pintype "bidirectional"))
    )
    (net (code "32") (name "/UART5_TX") (class "Default")
      (node (ref "H3") (pin "4") (pinfunction "4_4") (pintype "unspecified"))
      (node (ref "U13") (pin "80") (pinfunction "PC12_80") (pintype "bidirectional"))
    )
    (net (code "33") (name "/USART1_RX") (class "Default")
      (node (ref "U13") (pin "69") (pinfunction "PA10_69") (pintype "bidirectional"))
      (node (ref "U6") (pin "8") (pinfunction "8_8") (pintype "unspecified"))
    )
    (net (code "34") (name "/USART1_TX") (class "Default")
      (node (ref "U13") (pin "68") (pinfunction "PA9_68") (pintype "bidirectional"))
      (node (ref "U6") (pin "7") (pinfunction "7_7") (pintype "unspecified"))
    )
    (net (code "35") (name "/USART2_RX") (class "Default")
      (node (ref "U13") (pin "26") (pinfunction "PA3_26") (pintype "bidirectional"))
      (node (ref "U7") (pin "8") (pinfunction "8_8") (pintype "unspecified"))
    )
    (net (code "36") (name "/USART2_TX") (class "Default")
      (node (ref "U13") (pin "25") (pinfunction "PA2_25") (pintype "bidirectional"))
      (node (ref "U7") (pin "7") (pinfunction "7_7") (pintype "unspecified"))
    )
    (net (code "37") (name "/USART3_RX") (class "Default")
      (node (ref "U13") (pin "48") (pinfunction "PB11_48") (pintype "bidirectional"))
      (node (ref "U8") (pin "8") (pinfunction "8_8") (pintype "unspecified"))
    )
    (net (code "38") (name "/USART3_TX") (class "Default")
      (node (ref "U13") (pin "47") (pinfunction "PB10_47") (pintype "bidirectional"))
      (node (ref "U8") (pin "7") (pinfunction "7_7") (pintype "unspecified"))
    )
    (net (code "39") (name "/USART6_RX") (class "Default")
      (node (ref "H8") (pin "2") (pinfunction "2_2") (pintype "unspecified"))
      (node (ref "U13") (pin "64") (pinfunction "PC7_64") (pintype "bidirectional"))
    )
    (net (code "40") (name "/USART6_TX") (class "Default")
      (node (ref "H8") (pin "3") (pinfunction "3_3") (pintype "unspecified"))
      (node (ref "U13") (pin "63") (pinfunction "PC6_63") (pintype "bidirectional"))
    )
    (net (code "41") (name "3.3V") (class "Default")
      (node (ref "C25") (pin "2") (pinfunction "2_2") (pintype "input"))
      (node (ref "C26") (pin "2") (pinfunction "2_2") (pintype "input"))
      (node (ref "C28") (pin "2") (pinfunction "2_2") (pintype "input"))
      (node (ref "C29") (pin "2") (pinfunction "2_2") (pintype "input"))
      (node (ref "C30") (pin "2") (pinfunction "2_2") (pintype "input"))
      (node (ref "C31") (pin "2") (pinfunction "2_2") (pintype "input"))
      (node (ref "C32") (pin "2") (pinfunction "2_2") (pintype "input"))
      (node (ref "C33") (pin "2") (pinfunction "2_2") (pintype "input"))
      (node (ref "H1") (pin "1") (pinfunction "1_1") (pintype "unspecified"))
      (node (ref "H4") (pin "10") (pinfunction "10_10") (pintype "unspecified"))
      (node (ref "H4") (pin "2") (pinfunction "2_2") (pintype "unspecified"))
      (node (ref "H4") (pin "4") (pinfunction "4_4") (pintype "unspecified"))
      (node (ref "H4") (pin "6") (pinfunction "6_6") (pintype "unspecified"))
      (node (ref "H4") (pin "8") (pinfunction "8_8") (pintype "unspecified"))
      (node (ref "R12") (pin "1") (pinfunction "1_1") (pintype "input"))
      (node (ref "R7") (pin "2") (pinfunction "2_2") (pintype "input"))
      (node (ref "R8") (pin "2") (pinfunction "2_2") (pintype "input"))
      (node (ref "U12") (pin "2") (pinfunction "2_2") (pintype "unspecified"))
      (node (ref "U13") (pin "100") (pinfunction "VDD_100") (pintype "unspecified"))
      (node (ref "U13") (pin "11") (pinfunction "VDD_11") (pintype "unspecified"))
      (node (ref "U13") (pin "19") (pinfunction "VDD_19") (pintype "unspecified"))
      (node (ref "U13") (pin "21") (pinfunction "VREF+_21") (pintype "unspecified"))
      (node (ref "U13") (pin "28") (pinfunction "VDD_28") (pintype "unspecified"))
      (node (ref "U13") (pin "50") (pinfunction "VDD_50") (pintype "unspecified"))
      (node (ref "U13") (pin "6") (pinfunction "VBAT_6") (pintype "unspecified"))
      (node (ref "U13") (pin "75") (pinfunction "VDD_75") (pintype "unspecified"))
      (node (ref "U3") (pin "2") (pinfunction "VOUT_2") (pintype "unspecified"))
      (node (ref "U3") (pin "4") (pinfunction "VOUT_4") (pintype "unspecified"))
    )
    (net (code "42") (name "5V") (class "Default")
      (node (ref "C17") (pin "1") (pinfunction "1_1") (pintype "input"))
      (node (ref "C18") (pin "1") (pinfunction "1_1") (pintype "input"))
      (node (ref "C19") (pin "1") (pinfunction "1_1") (pintype "input"))
      (node (ref "C20") (pin "2") (pinfunction "2_2") (pintype "input"))
      (node (ref "C22") (pin "1") (pinfunction "1_1") (pintype "input"))
      (node (ref "C23") (pin "1") (pinfunction "1_1") (pintype "input"))
      (node (ref "C24") (pin "1") (pinfunction "1_1") (pintype "input"))
      (node (ref "H2") (pin "10") (pinfunction "10_10") (pintype "unspecified"))
      (node (ref "H2") (pin "3") (pinfunction "3_3") (pintype "unspecified"))
      (node (ref "H2") (pin "4") (pinfunction "4_4") (pintype "unspecified"))
      (node (ref "H2") (pin "9") (pinfunction "9_9") (pintype "unspecified"))
      (node (ref "H3") (pin "2") (pinfunction "2_2") (pintype "unspecified"))
      (node (ref "H4") (pin "1") (pinfunction "1_1") (pintype "unspecified"))
      (node (ref "H4") (pin "3") (pinfunction "3_3") (pintype "unspecified"))
      (node (ref "H4") (pin "5") (pinfunction "5_5") (pintype "unspecified"))
      (node (ref "H4") (pin "7") (pinfunction "7_7") (pintype "unspecified"))
      (node (ref "H4") (pin "9") (pinfunction "9_9") (pintype "unspecified"))
      (node (ref "H8") (pin "4") (pinfunction "4_4") (pintype "unspecified"))
      (node (ref "L4") (pin "2") (pinfunction "2_2") (pintype "unspecified"))
      (node (ref "R4") (pin "2") (pinfunction "2_2") (pintype "input"))
      (node (ref "R5") (pin "2") (pinfunction "2_2") (pintype "input"))
      (node (ref "U3") (pin "3") (pinfunction "VIN_3") (pintype "unspecified"))
    )
    (net (code "43") (name "12V") (class "Default")
      (node (ref "C10") (pin "2") (pinfunction "2_2") (pintype "input"))
      (node (ref "C6") (pin "1") (pinfunction "1_1") (pintype "input"))
      (node (ref "C7") (pin "1") (pinfunction "1_1") (pintype "input"))
      (node (ref "C8") (pin "1") (pinfunction "1_1") (pintype "input"))
      (node (ref "C9") (pin "1") (pinfunction "1_1") (pintype "input"))
      (node (ref "H9") (pin "10") (pinfunction "10_10") (pintype "unspecified"))
      (node (ref "H9") (pin "2") (pinfunction "2_2") (pintype "unspecified"))
      (node (ref "H9") (pin "4") (pinfunction "4_4") (pintype "unspecified"))
      (node (ref "H9") (pin "6") (pinfunction "6_6") (pintype "unspecified"))
      (node (ref "H9") (pin "8") (pinfunction "8_8") (pintype "unspecified"))
      (node (ref "L3") (pin "2") (pinfunction "2_2") (pintype "unspecified"))
      (node (ref "R1") (pin "2") (pinfunction "2_2") (pintype "input"))
      (node (ref "R2") (pin "2") (pinfunction "2_2") (pintype "input"))
    )
    (net (code "44") (name "16V") (class "Default")
      (node (ref "C1") (pin "1") (pinfunction "1_1") (pintype "input"))
      (node (ref "C12") (pin "1") (pinfunction "1_1") (pintype "input"))
      (node (ref "C13") (pin "1") (pinfunction "1_1") (pintype "input"))
      (node (ref "C14") (pin "1") (pinfunction "1_1") (pintype "input"))
      (node (ref "C15") (pin "1") (pinfunction "1_1") (pintype "input"))
      (node (ref "C2") (pin "1") (pinfunction "1_1") (pintype "input"))
      (node (ref "C3") (pin "1") (pinfunction "1_1") (pintype "input"))
      (node (ref "C4") (pin "1") (pinfunction "1_1") (pintype "input"))
      (node (ref "D1") (pin "1") (pinfunction "K_1") (pintype "unspecified"))
      (node (ref "D3") (pin "1") (pinfunction "K_1") (pintype "unspecified"))
      (node (ref "SW2") (pin "2") (pinfunction "2_2") (pintype "input"))
      (node (ref "U1") (pin "7") (pinfunction "VIN_7") (pintype "input"))
      (node (ref "U2") (pin "7") (pinfunction "VIN_7") (pintype "input"))
      (node (ref "U6") (pin "1") (pinfunction "1_1") (pintype "unspecified"))
      (node (ref "U7") (pin "1") (pinfunction "1_1") (pintype "unspecified"))
      (node (ref "U8") (pin "1") (pinfunction "1_1") (pintype "unspecified"))
      (node (ref "U9") (pin "1") (pinfunction "1_1") (pintype "unspecified"))
    )
    (net (code "45") (name "GND") (class "Default")
      (node (ref "C1") (pin "2") (pinfunction "2_2") (pintype "input"))
      (node (ref "C11") (pin "1") (pinfunction "1_1") (pintype "input"))
      (node (ref "C12") (pin "2") (pinfunction "2_2") (pintype "input"))
      (node (ref "C13") (pin "2") (pinfunction "2_2") (pintype "input"))
      (node (ref "C14") (pin "2") (pinfunction "2_2") (pintype "input"))
      (node (ref "C15") (pin "2") (pinfunction "2_2") (pintype "input"))
      (node (ref "C17") (pin "2") (pinfunction "2_2") (pintype "input"))
      (node (ref "C18") (pin "2") (pinfunction "2_2") (pintype "input"))
      (node (ref "C19") (pin "2") (pinfunction "2_2") (pintype "input"))
      (node (ref "C2") (pin "2") (pinfunction "2_2") (pintype "input"))
      (node (ref "C21") (pin "1") (pinfunction "1_1") (pintype "input"))
      (node (ref "C22") (pin "2") (pinfunction "2_2") (pintype "input"))
      (node (ref "C23") (pin "2") (pinfunction "2_2") (pintype "input"))
      (node (ref "C24") (pin "2") (pinfunction "2_2") (pintype "input"))
      (node (ref "C25") (pin "1") (pinfunction "1_1") (pintype "input"))
      (node (ref "C26") (pin "1") (pinfunction "1_1") (pintype "input"))
      (node (ref "C27") (pin "1") (pinfunction "1_1") (pintype "input"))
      (node (ref "C28") (pin "1") (pinfunction "1_1") (pintype "input"))
      (node (ref "C29") (pin "1") (pinfunction "1_1") (pintype "input"))
      (node (ref "C3") (pin "2") (pinfunction "2_2") (pintype "input"))
      (node (ref "C30") (pin "1") (pinfunction "1_1") (pintype "input"))
      (node (ref "C31") (pin "1") (pinfunction "1_1") (pintype "input"))
      (node (ref "C32") (pin "1") (pinfunction "1_1") (pintype "input"))
      (node (ref "C33") (pin "1") (pinfunction "1_1") (pintype "input"))
      (node (ref "C34") (pin "2") (pinfunction "2_2") (pintype "input"))
      (node (ref "C35") (pin "2") (pinfunction "2_2") (pintype "input"))
      (node (ref "C36") (pin "1") (pinfunction "1_1") (pintype "input"))
      (node (ref "C38") (pin "1") (pinfunction "1_1") (pintype "input"))
      (node (ref "C39") (pin "2") (pinfunction "2_2") (pintype "input"))
      (node (ref "C4") (pin "2") (pinfunction "2_2") (pintype "input"))
      (node (ref "C40") (pin "2") (pinfunction "2_2") (pintype "input"))
      (node (ref "C41") (pin "1") (pinfunction "1_1") (pintype "input"))
      (node (ref "C42") (pin "1") (pinfunction "1_1") (pintype "input"))
      (node (ref "C6") (pin "2") (pinfunction "2_2") (pintype "input"))
      (node (ref "C7") (pin "2") (pinfunction "2_2") (pintype "input"))
      (node (ref "C8") (pin "2") (pinfunction "2_2") (pintype "input"))
      (node (ref "C9") (pin "2") (pinfunction "2_2") (pintype "input"))
      (node (ref "CN1") (pin "1") (pinfunction "-_1") (pintype "unspecified"))
      (node (ref "D1") (pin "2") (pinfunction "A_2") (pintype "unspecified"))
      (node (ref "D2") (pin "2") (pinfunction "A_2") (pintype "unspecified"))
      (node (ref "D3") (pin "2") (pinfunction "A_2") (pintype "unspecified"))
      (node (ref "D4") (pin "2") (pinfunction "A_2") (pintype "unspecified"))
      (node (ref "H1") (pin "4") (pinfunction "4_4") (pintype "unspecified"))
      (node (ref "H2") (pin "11") (pinfunction "11_11") (pintype "unspecified"))
      (node (ref "H2") (pin "12") (pinfunction "12_12") (pintype "unspecified"))
      (node (ref "H2") (pin "5") (pinfunction "5_5") (pintype "unspecified"))
      (node (ref "H2") (pin "6") (pinfunction "6_6") (pintype "unspecified"))
      (node (ref "H3") (pin "5") (pinfunction "5_5") (pintype "unspecified"))
      (node (ref "H8") (pin "1") (pinfunction "1_1") (pintype "unspecified"))
      (node (ref "H9") (pin "1") (pinfunction "1_1") (pintype "unspecified"))
      (node (ref "H9") (pin "3") (pinfunction "3_3") (pintype "unspecified"))
      (node (ref "H9") (pin "5") (pinfunction "5_5") (pintype "unspecified"))
      (node (ref "H9") (pin "7") (pinfunction "7_7") (pintype "unspecified"))
      (node (ref "H9") (pin "9") (pinfunction "9_9") (pintype "unspecified"))
      (node (ref "LED1") (pin "2") (pinfunction "-_2") (pintype "unspecified"))
      (node (ref "LED2") (pin "2") (pinfunction "-_2") (pintype "unspecified"))
      (node (ref "LED3") (pin "2") (pinfunction "-_2") (pintype "unspecified"))
      (node (ref "LED4") (pin "2") (pinfunction "-_2") (pintype "unspecified"))
      (node (ref "R10") (pin "2") (pinfunction "2_2") (pintype "input"))
      (node (ref "R3") (pin "1") (pinfunction "1_1") (pintype "input"))
      (node (ref "R6") (pin "1") (pinfunction "1_1") (pintype "input"))
      (node (ref "R9") (pin "2") (pinfunction "2_2") (pintype "input"))
      (node (ref "SW1") (pin "1") (pinfunction "1_1") (pintype "unspecified"))
      (node (ref "SW3") (pin "2") (pinfunction "2_2") (pintype "unspecified"))
      (node (ref "SW4") (pin "2") (pinfunction "2_2") (pintype "unspecified"))
      (node (ref "SW5") (pin "2") (pinfunction "2_2") (pintype "unspecified"))
      (node (ref "SW6") (pin "2") (pinfunction "2_2") (pintype "unspecified"))
      (node (ref "U1") (pin "6") (pinfunction "GND_6") (pintype "unspecified"))
      (node (ref "U1") (pin "9") (pinfunction "EP_9") (pintype "unspecified"))
      (node (ref "U12") (pin "1") (pinfunction "1_1") (pintype "unspecified"))
      (node (ref "U13") (pin "10") (pinfunction "VSS_10") (pintype "unspecified"))
      (node (ref "U13") (pin "20") (pinfunction "VSSA_20") (pintype "unspecified"))
      (node (ref "U13") (pin "27") (pinfunction "VSS_27") (pintype "unspecified"))
      (node (ref "U13") (pin "74") (pinfunction "VSS_74") (pintype "unspecified"))
      (node (ref "U13") (pin "99") (pinfunction "VSS_99") (pintype "unspecified"))
      (node (ref "U2") (pin "6") (pinfunction "GND_6") (pintype "unspecified"))
      (node (ref "U2") (pin "9") (pinfunction "EP_9") (pintype "unspecified"))
      (node (ref "U3") (pin "1") (pinfunction "GND_1") (pintype "unspecified"))
      (node (ref "U6") (pin "2") (pinfunction "2_2") (pintype "unspecified"))
      (node (ref "U7") (pin "2") (pinfunction "2_2") (pintype "unspecified"))
      (node (ref "U8") (pin "2") (pinfunction "2_2") (pintype "unspecified"))
      (node (ref "U9") (pin "2") (pinfunction "2_2") (pintype "unspecified"))
    )
    (net (code "46") (name "Net-(CN1-+)") (class "Default")
      (node (ref "CN1") (pin "2") (pinfunction "+_2") (pintype "unspecified"))
      (node (ref "SW2") (pin "1") (pinfunction "1_1") (pintype "input"))
    )
    (net (code "47") (name "Net-(D2-K)") (class "Default")
      (node (ref "C5") (pin "2") (pinfunction "2_2") (pintype "input"))
      (node (ref "D2") (pin "1") (pinfunction "K_1") (pintype "unspecified"))
      (node (ref "L3") (pin "1") (pinfunction "1_1") (pintype "unspecified"))
      (node (ref "U1") (pin "8") (pinfunction "PH_8") (pintype "output"))
    )
    (net (code "48") (name "Net-(D4-K)") (class "Default")
      (node (ref "C16") (pin "1") (pinfunction "1_1") (pintype "input"))
      (node (ref "D4") (pin "1") (pinfunction "K_1") (pintype "unspecified"))
      (node (ref "L4") (pin "1") (pinfunction "1_1") (pintype "unspecified"))
      (node (ref "U2") (pin "8") (pinfunction "PH_8") (pintype "output"))
    )
    (net (code "49") (name "Net-(LED1-+)") (class "Default")
      (node (ref "LED1") (pin "1") (pinfunction "+_1") (pintype "unspecified"))
      (node (ref "R2") (pin "1") (pinfunction "1_1") (pintype "input"))
    )
    (net (code "50") (name "Net-(LED2-+)") (class "Default")
      (node (ref "LED2") (pin "1") (pinfunction "+_1") (pintype "unspecified"))
      (node (ref "R5") (pin "1") (pinfunction "1_1") (pintype "input"))
    )
    (net (code "51") (name "Net-(LED3-+)") (class "Default")
      (node (ref "LED3") (pin "1") (pinfunction "+_1") (pintype "unspecified"))
      (node (ref "R7") (pin "1") (pinfunction "1_1") (pintype "input"))
    )
    (net (code "52") (name "Net-(LED4-+)") (class "Default")
      (node (ref "LED4") (pin "1") (pinfunction "+_1") (pintype "unspecified"))
      (node (ref "R11") (pin "1") (pinfunction "1_1") (pintype "input"))
    )
    (net (code "53") (name "Net-(U1-BOOT)") (class "Default")
      (node (ref "C5") (pin "1") (pinfunction "1_1") (pintype "input"))
      (node (ref "U1") (pin "1") (pinfunction "BOOT_1") (pintype "unspecified"))
    )
    (net (code "54") (name "Net-(U1-VSENSE)") (class "Default")
      (node (ref "C10") (pin "1") (pinfunction "1_1") (pintype "input"))
      (node (ref "C11") (pin "2") (pinfunction "2_2") (pintype "input"))
      (node (ref "R1") (pin "1") (pinfunction "1_1") (pintype "input"))
      (node (ref "R3") (pin "2") (pinfunction "2_2") (pintype "input"))
      (node (ref "U1") (pin "4") (pinfunction "VSENSE_4") (pintype "output"))
    )
    (net (code "55") (name "Net-(U2-BOOT)") (class "Default")
      (node (ref "C16") (pin "2") (pinfunction "2_2") (pintype "input"))
      (node (ref "U2") (pin "1") (pinfunction "BOOT_1") (pintype "unspecified"))
    )
    (net (code "56") (name "Net-(U2-VSENSE)") (class "Default")
      (node (ref "C20") (pin "1") (pinfunction "1_1") (pintype "input"))
      (node (ref "C21") (pin "2") (pinfunction "2_2") (pintype "input"))
      (node (ref "R4") (pin "1") (pinfunction "1_1") (pintype "input"))
      (node (ref "R6") (pin "2") (pinfunction "2_2") (pintype "input"))
      (node (ref "U2") (pin "4") (pinfunction "VSENSE_4") (pintype "output"))
    )
    (net (code "57") (name "Net-(U13A-VCAP_1)") (class "Default")
      (node (ref "C39") (pin "1") (pinfunction "1_1") (pintype "input"))
      (node (ref "U13") (pin "49") (pinfunction "VCAP_1_49") (pintype "unspecified"))
    )
    (net (code "58") (name "Net-(U13A-VCAP_2)") (class "Default")
      (node (ref "C40") (pin "1") (pinfunction "1_1") (pintype "input"))
      (node (ref "U13") (pin "73") (pinfunction "VCAP_2_73") (pintype "unspecified"))
    )
    (net (code "59") (name "Net-(U13B-VDDA)") (class "Default")
      (node (ref "C41") (pin "2") (pinfunction "2_2") (pintype "input"))
      (node (ref "C42") (pin "2") (pinfunction "2_2") (pintype "input"))
      (node (ref "R12") (pin "2") (pinfunction "2_2") (pintype "input"))
      (node (ref "U13") (pin "22") (pinfunction "VDDA_22") (pintype "unspecified"))
    )
    (net (code "60") (name "unconnected-(CN1-Pad3)") (class "Default")
      (node (ref "CN1") (pin "3") (pinfunction "3_3") (pintype "unspecified+no_connect"))
    )
    (net (code "61") (name "unconnected-(CN1-Pad4)") (class "Default")
      (node (ref "CN1") (pin "4") (pinfunction "4_4") (pintype "unspecified+no_connect"))
    )
    (net (code "62") (name "unconnected-(H3-Pad1)") (class "Default")
      (node (ref "H3") (pin "1") (pinfunction "1_1") (pintype "unspecified+no_connect"))
    )
    (net (code "63") (name "unconnected-(H3-Pad6)") (class "Default")
      (node (ref "H3") (pin "6") (pinfunction "6_6") (pintype "unspecified+no_connect"))
    )
    (net (code "64") (name "unconnected-(H6-Pad9)") (class "Default")
      (node (ref "H6") (pin "9") (pinfunction "9_9") (pintype "unspecified+no_connect"))
    )
    (net (code "65") (name "unconnected-(H6-Pad10)") (class "Default")
      (node (ref "H6") (pin "10") (pinfunction "10_10") (pintype "unspecified+no_connect"))
    )
    (net (code "66") (name "unconnected-(H7-Pad1)") (class "Default")
      (node (ref "H7") (pin "1") (pinfunction "1_1") (pintype "unspecified+no_connect"))
    )
    (net (code "67") (name "unconnected-(H7-Pad2)") (class "Default")
      (node (ref "H7") (pin "2") (pinfunction "2_2") (pintype "unspecified+no_connect"))
    )
    (net (code "68") (name "unconnected-(H7-Pad3)") (class "Default")
      (node (ref "H7") (pin "3") (pinfunction "3_3") (pintype "unspecified+no_connect"))
    )
    (net (code "69") (name "unconnected-(H7-Pad4)") (class "Default")
      (node (ref "H7") (pin "4") (pinfunction "4_4") (pintype "unspecified+no_connect"))
    )
    (net (code "70") (name "unconnected-(H7-Pad5)") (class "Default")
      (node (ref "H7") (pin "5") (pinfunction "5_5") (pintype "unspecified+no_connect"))
    )
    (net (code "71") (name "unconnected-(H7-Pad6)") (class "Default")
      (node (ref "H7") (pin "6") (pinfunction "6_6") (pintype "unspecified+no_connect"))
    )
    (net (code "72") (name "unconnected-(U1-ENA-Pad5)") (class "Default")
      (node (ref "U1") (pin "5") (pinfunction "ENA_5") (pintype "input+no_connect"))
    )
    (net (code "73") (name "unconnected-(U1-NC-Pad2)") (class "Default")
      (node (ref "U1") (pin "2") (pinfunction "NC_2") (pintype "unspecified+no_connect"))
    )
    (net (code "74") (name "unconnected-(U1-NC-Pad3)") (class "Default")
      (node (ref "U1") (pin "3") (pinfunction "NC_3") (pintype "unspecified+no_connect"))
    )
    (net (code "75") (name "unconnected-(U2-ENA-Pad5)") (class "Default")
      (node (ref "U2") (pin "5") (pinfunction "ENA_5") (pintype "input+no_connect"))
    )
    (net (code "76") (name "unconnected-(U2-NC-Pad2)") (class "Default")
      (node (ref "U2") (pin "2") (pinfunction "NC_2") (pintype "unspecified+no_connect"))
    )
    (net (code "77") (name "unconnected-(U2-NC-Pad3)") (class "Default")
      (node (ref "U2") (pin "3") (pinfunction "NC_3") (pintype "unspecified+no_connect"))
    )
    (net (code "78") (name "unconnected-(U6-Pad3)") (class "Default")
      (node (ref "U6") (pin "3") (pinfunction "3_3") (pintype "unspecified+no_connect"))
    )
    (net (code "79") (name "unconnected-(U6-Pad4)") (class "Default")
      (node (ref "U6") (pin "4") (pinfunction "4_4") (pintype "unspecified+no_connect"))
    )
    (net (code "80") (name "unconnected-(U6-Pad5)") (class "Default")
      (node (ref "U6") (pin "5") (pinfunction "5_5") (pintype "unspecified+no_connect"))
    )
    (net (code "81") (name "unconnected-(U6-Pad6)") (class "Default")
      (node (ref "U6") (pin "6") (pinfunction "6_6") (pintype "unspecified+no_connect"))
    )
    (net (code "82") (name "unconnected-(U7-Pad3)") (class "Default")
      (node (ref "U7") (pin "3") (pinfunction "3_3") (pintype "unspecified+no_connect"))
    )
    (net (code "83") (name "unconnected-(U7-Pad4)") (class "Default")
      (node (ref "U7") (pin "4") (pinfunction "4_4") (pintype "unspecified+no_connect"))
    )
    (net (code "84") (name "unconnected-(U7-Pad5)") (class "Default")
      (node (ref "U7") (pin "5") (pinfunction "5_5") (pintype "unspecified+no_connect"))
    )
    (net (code "85") (name "unconnected-(U7-Pad6)") (class "Default")
      (node (ref "U7") (pin "6") (pinfunction "6_6") (pintype "unspecified+no_connect"))
    )
    (net (code "86") (name "unconnected-(U8-Pad3)") (class "Default")
      (node (ref "U8") (pin "3") (pinfunction "3_3") (pintype "unspecified+no_connect"))
    )
    (net (code "87") (name "unconnected-(U8-Pad4)") (class "Default")
      (node (ref "U8") (pin "4") (pinfunction "4_4") (pintype "unspecified+no_connect"))
    )
    (net (code "88") (name "unconnected-(U8-Pad5)") (class "Default")
      (node (ref "U8") (pin "5") (pinfunction "5_5") (pintype "unspecified+no_connect"))
    )
    (net (code "89") (name "unconnected-(U8-Pad6)") (class "Default")
      (node (ref "U8") (pin "6") (pinfunction "6_6") (pintype "unspecified+no_connect"))
    )
    (net (code "90") (name "unconnected-(U9-Pad3)") (class "Default")
      (node (ref "U9") (pin "3") (pinfunction "3_3") (pintype "unspecified+no_connect"))
    )
    (net (code "91") (name "unconnected-(U9-Pad4)") (class "Default")
      (node (ref "U9") (pin "4") (pinfunction "4_4") (pintype "unspecified+no_connect"))
    )
    (net (code "92") (name "unconnected-(U9-Pad5)") (class "Default")
      (node (ref "U9") (pin "5") (pinfunction "5_5") (pintype "unspecified+no_connect"))
    )
    (net (code "93") (name "unconnected-(U9-Pad6)") (class "Default")
      (node (ref "U9") (pin "6") (pinfunction "6_6") (pintype "unspecified+no_connect"))
    )
    (net (code "94") (name "unconnected-(U13A-PA8-Pad67)") (class "Default")
      (node (ref "U13") (pin "67") (pinfunction "PA8_67") (pintype "bidirectional+no_connect"))
    )
    (net (code "95") (name "unconnected-(U13A-PA11-Pad70)") (class "Default")
      (node (ref "U13") (pin "70") (pinfunction "PA11_70") (pintype "bidirectional+no_connect"))
    )
    (net (code "96") (name "unconnected-(U13A-PA12-Pad71)") (class "Default")
      (node (ref "U13") (pin "71") (pinfunction "PA12_71") (pintype "bidirectional+no_connect"))
    )
    (net (code "97") (name "unconnected-(U13A-PA15(JTDI)-Pad77)") (class "Default")
      (node (ref "U13") (pin "77") (pinfunction "PA15(JTDI)_77") (pintype "bidirectional+no_connect"))
    )
    (net (code "98") (name "unconnected-(U13A-PB3(JTDOTRACESWO)-Pad89)") (class "Default")
      (node (ref "U13") (pin "89") (pinfunction "PB3(JTDOTRACESWO)_89") (pintype "bidirectional+no_connect"))
    )
    (net (code "99") (name "unconnected-(U13A-PB4(NJTRST)-Pad90)") (class "Default")
      (node (ref "U13") (pin "90") (pinfunction "PB4(NJTRST)_90") (pintype "bidirectional+no_connect"))
    )
    (net (code "100") (name "unconnected-(U13A-PB5-Pad91)") (class "Default")
      (node (ref "U13") (pin "91") (pinfunction "PB5_91") (pintype "bidirectional+no_connect"))
    )
    (net (code "101") (name "unconnected-(U13A-PB12-Pad51)") (class "Default")
      (node (ref "U13") (pin "51") (pinfunction "PB12_51") (pintype "bidirectional+no_connect"))
    )
    (net (code "102") (name "unconnected-(U13A-PB13-Pad52)") (class "Default")
      (node (ref "U13") (pin "52") (pinfunction "PB13_52") (pintype "bidirectional+no_connect"))
    )
    (net (code "103") (name "unconnected-(U13A-PB14-Pad53)") (class "Default")
      (node (ref "U13") (pin "53") (pinfunction "PB14_53") (pintype "bidirectional+no_connect"))
    )
    (net (code "104") (name "unconnected-(U13A-PB15-Pad54)") (class "Default")
      (node (ref "U13") (pin "54") (pinfunction "PB15_54") (pintype "bidirectional+no_connect"))
    )
    (net (code "105") (name "unconnected-(U13A-PC0-Pad15)") (class "Default")
      (node (ref "U13") (pin "15") (pinfunction "PC0_15") (pintype "bidirectional+no_connect"))
    )
    (net (code "106") (name "unconnected-(U13A-PC1-Pad16)") (class "Default")
      (node (ref "U13") (pin "16") (pinfunction "PC1_16") (pintype "bidirectional+no_connect"))
    )
    (net (code "107") (name "unconnected-(U13A-PC2-Pad17)") (class "Default")
      (node (ref "U13") (pin "17") (pinfunction "PC2_17") (pintype "bidirectional+no_connect"))
    )
    (net (code "108") (name "unconnected-(U13A-PC3-Pad18)") (class "Default")
      (node (ref "U13") (pin "18") (pinfunction "PC3_18") (pintype "bidirectional+no_connect"))
    )
    (net (code "109") (name "unconnected-(U13A-PC9-Pad66)") (class "Default")
      (node (ref "U13") (pin "66") (pinfunction "PC9_66") (pintype "bidirectional+no_connect"))
    )
    (net (code "110") (name "unconnected-(U13A-PC10-Pad78)") (class "Default")
      (node (ref "U13") (pin "78") (pinfunction "PC10_78") (pintype "bidirectional+no_connect"))
    )
    (net (code "111") (name "unconnected-(U13A-PC11-Pad79)") (class "Default")
      (node (ref "U13") (pin "79") (pinfunction "PC11_79") (pintype "bidirectional+no_connect"))
    )
    (net (code "112") (name "unconnected-(U13A-PC13-Pad7)") (class "Default")
      (node (ref "U13") (pin "7") (pinfunction "PC13_7") (pintype "bidirectional+no_connect"))
    )
    (net (code "113") (name "unconnected-(U13A-PD0-Pad81)") (class "Default")
      (node (ref "U13") (pin "81") (pinfunction "PD0_81") (pintype "bidirectional+no_connect"))
    )
    (net (code "114") (name "unconnected-(U13A-PD1-Pad82)") (class "Default")
      (node (ref "U13") (pin "82") (pinfunction "PD1_82") (pintype "bidirectional+no_connect"))
    )
    (net (code "115") (name "unconnected-(U13A-PD3-Pad84)") (class "Default")
      (node (ref "U13") (pin "84") (pinfunction "PD3_84") (pintype "bidirectional+no_connect"))
    )
    (net (code "116") (name "unconnected-(U13A-PD4-Pad85)") (class "Default")
      (node (ref "U13") (pin "85") (pinfunction "PD4_85") (pintype "bidirectional+no_connect"))
    )
    (net (code "117") (name "unconnected-(U13A-PD5-Pad86)") (class "Default")
      (node (ref "U13") (pin "86") (pinfunction "PD5_86") (pintype "bidirectional+no_connect"))
    )
    (net (code "118") (name "unconnected-(U13A-PD6-Pad87)") (class "Default")
      (node (ref "U13") (pin "87") (pinfunction "PD6_87") (pintype "bidirectional+no_connect"))
    )
    (net (code "119") (name "unconnected-(U13A-PD7-Pad88)") (class "Default")
      (node (ref "U13") (pin "88") (pinfunction "PD7_88") (pintype "bidirectional+no_connect"))
    )
    (net (code "120") (name "unconnected-(U13A-PD8-Pad55)") (class "Default")
      (node (ref "U13") (pin "55") (pinfunction "PD8_55") (pintype "bidirectional+no_connect"))
    )
    (net (code "121") (name "unconnected-(U13A-PD9-Pad56)") (class "Default")
      (node (ref "U13") (pin "56") (pinfunction "PD9_56") (pintype "bidirectional+no_connect"))
    )
    (net (code "122") (name "unconnected-(U13A-PD10-Pad57)") (class "Default")
      (node (ref "U13") (pin "57") (pinfunction "PD10_57") (pintype "bidirectional+no_connect"))
    )
    (net (code "123") (name "unconnected-(U13A-PD11-Pad58)") (class "Default")
      (node (ref "U13") (pin "58") (pinfunction "PD11_58") (pintype "bidirectional+no_connect"))
    )
    (net (code "124") (name "unconnected-(U13A-PE2-Pad1)") (class "Default")
      (node (ref "U13") (pin "1") (pinfunction "PE2_1") (pintype "bidirectional+no_connect"))
    )
    (net (code "125") (name "unconnected-(U13A-PE3-Pad2)") (class "Default")
      (node (ref "U13") (pin "2") (pinfunction "PE3_2") (pintype "bidirectional+no_connect"))
    )
    (net (code "126") (name "unconnected-(U13A-PE4-Pad3)") (class "Default")
      (node (ref "U13") (pin "3") (pinfunction "PE4_3") (pintype "bidirectional+no_connect"))
    )
    (net (code "127") (name "unconnected-(U13A-PE5-Pad4)") (class "Default")
      (node (ref "U13") (pin "4") (pinfunction "PE5_4") (pintype "bidirectional+no_connect"))
    )
    (net (code "128") (name "unconnected-(U13A-PE6-Pad5)") (class "Default")
      (node (ref "U13") (pin "5") (pinfunction "PE6_5") (pintype "bidirectional+no_connect"))
    )
    (net (code "129") (name "unconnected-(U13A-PE7-Pad38)") (class "Default")
      (node (ref "U13") (pin "38") (pinfunction "PE7_38") (pintype "bidirectional+no_connect"))
    )
    (net (code "130") (name "unconnected-(U13A-PE8-Pad39)") (class "Default")
      (node (ref "U13") (pin "39") (pinfunction "PE8_39") (pintype "bidirectional+no_connect"))
    )
    (net (code "131") (name "unconnected-(U13A-PE9-Pad40)") (class "Default")
      (node (ref "U13") (pin "40") (pinfunction "PE9_40") (pintype "bidirectional+no_connect"))
    )
    (net (code "132") (name "unconnected-(U13A-PE10-Pad41)") (class "Default")
      (node (ref "U13") (pin "41") (pinfunction "PE10_41") (pintype "bidirectional+no_connect"))
    )
    (net (code "133") (name "unconnected-(U13A-PE11-Pad42)") (class "Default")
      (node (ref "U13") (pin "42") (pinfunction "PE11_42") (pintype "bidirectional+no_connect"))
    )
    (net (code "134") (name "unconnected-(U13A-PE12-Pad43)") (class "Default")
      (node (ref "U13") (pin "43") (pinfunction "PE12_43") (pintype "bidirectional+no_connect"))
    )
    (net (code "135") (name "unconnected-(U13A-PE13-Pad44)") (class "Default")
      (node (ref "U13") (pin "44") (pinfunction "PE13_44") (pintype "bidirectional+no_connect"))
    )
    (net (code "136") (name "unconnected-(U13A-PE14-Pad45)") (class "Default")
      (node (ref "U13") (pin "45") (pinfunction "PE14_45") (pintype "bidirectional+no_connect"))
    )
    (net (code "137") (name "unconnected-(U13A-PE15-Pad46)") (class "Default")
      (node (ref "U13") (pin "46") (pinfunction "PE15_46") (pintype "bidirectional+no_connect"))
    )
  )
)
